# I2C_SlipRing_v1.net
KiCad netlist of a schematic drawn in EAGLE
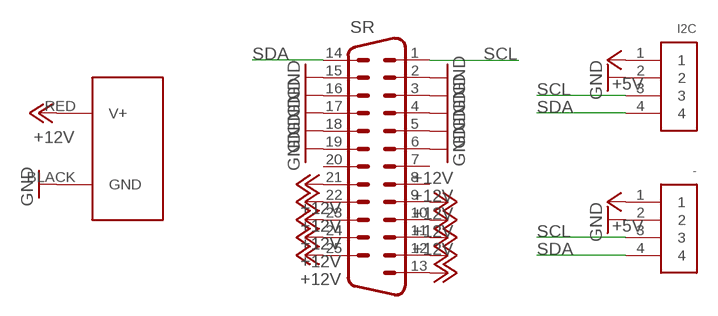
[diagram p0: schematic, sheet 1]

(export (version "E")
  (design (tool "Eeschema 10.0.6"))
  (components
    (comp (ref "-")
      (value "1X4-CLEANBIG")
      (footprint "eagle-import:1X04-CLEANBIG")
      (libsource (lib "eagle-import") (part "1X4-CLEANBIG"))
    )
    (comp (ref "I2C")
      (value "1X4-CLEANBIG")
      (footprint "eagle-import:1X04-CLEANBIG")
      (libsource (lib "eagle-import") (part "1X4-CLEANBIG"))
    )
    (comp (ref "J1")
      (value "POWERPOLE_POWER25A_HORIZONTAL_G2")
      (footprint "eagle-import:POWERPOLE_PAIR_25A_HORIZ_G2")
      (libsource (lib "eagle-import") (part "POWERPOLE_POWER25A_HORIZONTAL_G2"))
    )
    (comp (ref "SR")
      (value "DB25HP")
      (footprint "eagle-import:M25HP")
      (libsource (lib "eagle-import") (part "DB25HP"))
    )
  )
  (nets
    (net (code "1") (name "+5V") (class "Default")
      (node (ref "-") (pin "1") (pinfunction "1_1") (pintype "bidirectional"))
      (node (ref "I2C") (pin "1") (pinfunction "1_1") (pintype "bidirectional"))
    )
    (net (code "2") (name "+12V") (class "Default")
      (node (ref "J1") (pin "RED") (pinfunction "V+_RED") (pintype "power_in"))
      (node (ref "SR") (pin "10") (pinfunction "10_10") (pintype "passive"))
      (node (ref "SR") (pin "11") (pinfunction "11_11") (pintype "passive"))
      (node (ref "SR") (pin "12") (pinfunction "12_12") (pintype "passive"))
      (node (ref "SR") (pin "13") (pinfunction "13_13") (pintype "passive"))
      (node (ref "SR") (pin "21") (pinfunction "21_21") (pintype "passive"))
      (node (ref "SR") (pin "22") (pinfunction "22_22") (pintype "passive"))
      (node (ref "SR") (pin "23") (pinfunction "23_23") (pintype "passive"))
      (node (ref "SR") (pin "24") (pinfunction "24_24") (pintype "passive"))
      (node (ref "SR") (pin "25") (pinfunction "25_25") (pintype "passive"))
      (node (ref "SR") (pin "9") (pinfunction "9_9") (pintype "passive"))
    )
    (net (code "3") (name "/SCL") (class "Default")
      (node (ref "-") (pin "3") (pinfunction "3_3") (pintype "bidirectional"))
      (node (ref "I2C") (pin "3") (pinfunction "3_3") (pintype "bidirectional"))
      (node (ref "SR") (pin "1") (pinfunction "1_1") (pintype "passive"))
    )
    (net (code "4") (name "/SDA") (class "Default")
      (node (ref "-") (pin "4") (pinfunction "4_4") (pintype "bidirectional"))
      (node (ref "I2C") (pin "4") (pinfunction "4_4") (pintype "bidirectional"))
      (node (ref "SR") (pin "14") (pinfunction "14_14") (pintype "passive"))
    )
    (net (code "5") (name "GND") (class "Default")
      (node (ref "-") (pin "2") (pinfunction "2_2") (pintype "bidirectional"))
      (node (ref "I2C") (pin "2") (pinfunction "2_2") (pintype "bidirectional"))
      (node (ref "J1") (pin "BLACK") (pinfunction "GND_BLACK") (pintype "power_in"))
      (node (ref "SR") (pin "15") (pinfunction "15_15") (pintype "passive"))
      (node (ref "SR") (pin "16") (pinfunction "16_16") (pintype "passive"))
      (node (ref "SR") (pin "17") (pinfunction "17_17") (pintype "passive"))
      (node (ref "SR") (pin "18") (pinfunction "18_18") (pintype "passive"))
      (node (ref "SR") (pin "19") (pinfunction "19_19") (pintype "passive"))
      (node (ref "SR") (pin "2") (pinfunction "2_2") (pintype "passive"))
      (node (ref "SR") (pin "3") (pinfunction "3_3") (pintype "passive"))
      (node (ref "SR") (pin "4") (pinfunction "4_4") (pintype "passive"))
      (node (ref "SR") (pin "5") (pinfunction "5_5") (pintype "passive"))
      (node (ref "SR") (pin "6") (pinfunction "6_6") (pintype "passive"))
    )
    (net (code "6") (name "unconnected-(SR-Pad7)") (class "Default")
      (node (ref "SR") (pin "7") (pinfunction "7_7") (pintype "passive"))
    )
    (net (code "7") (name "unconnected-(SR-Pad8)") (class "Default")
      (node (ref "SR") (pin "8") (pinfunction "8_8") (pintype "passive"))
    )
    (net (code "8") (name "unconnected-(SR-Pad20)") (class "Default")
      (node (ref "SR") (pin "20") (pinfunction "20_20") (pintype "passive"))
    )
  )
)
